# KEY_1_0.net
KiCad netlist of a schematic drawn in EAGLE
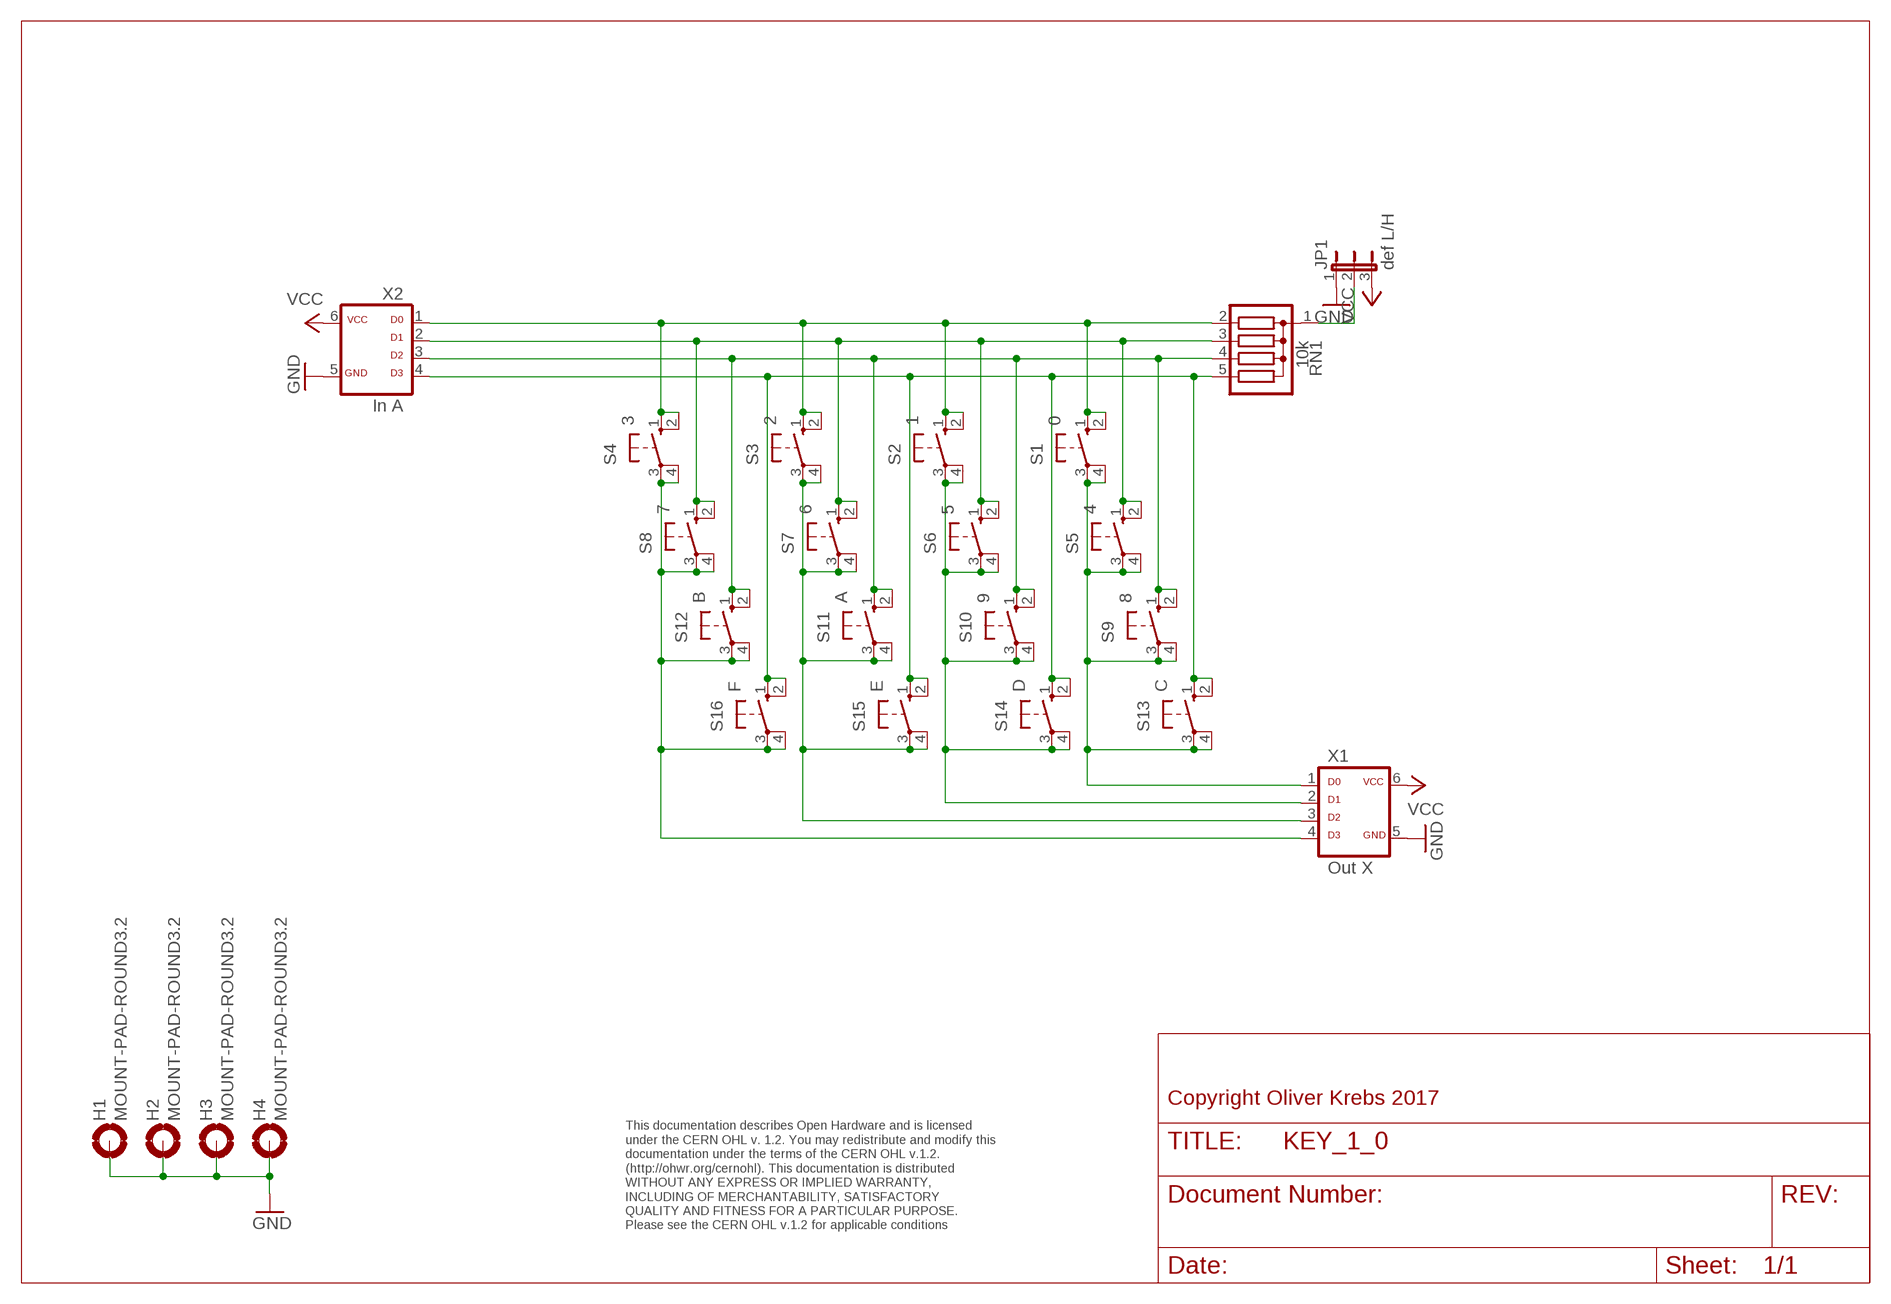
[diagram p0: schematic, sheet 1]

(export (version "E")
  (design (tool "Eeschema 10.0.6"))
  (components
    (comp (ref "H1")
      (value "MOUNT-PAD-ROUND3.2")
      (footprint "eagle-import:3,2-PAD")
      (libsource (lib "eagle-import") (part "MOUNT-PAD-ROUND3.2"))
    )
    (comp (ref "H2")
      (value "MOUNT-PAD-ROUND3.2")
      (footprint "eagle-import:3,2-PAD")
      (libsource (lib "eagle-import") (part "MOUNT-PAD-ROUND3.2"))
    )
    (comp (ref "H3")
      (value "MOUNT-PAD-ROUND3.2")
      (footprint "eagle-import:3,2-PAD")
      (libsource (lib "eagle-import") (part "MOUNT-PAD-ROUND3.2"))
    )
    (comp (ref "H4")
      (value "MOUNT-PAD-ROUND3.2")
      (footprint "eagle-import:3,2-PAD")
      (libsource (lib "eagle-import") (part "MOUNT-PAD-ROUND3.2"))
    )
    (comp (ref "JP1")
      (value "def L/H")
      (footprint "eagle-import:JP2-U")
      (libsource (lib "eagle-import") (part "JP2EJP2-U"))
    )
    (comp (ref "RN1")
      (value "10k")
      (footprint "eagle-import:SIL5")
      (libsource (lib "eagle-import") (part "G04R"))
    )
    (comp (ref "S1")
      (value "0")
      (footprint "eagle-import:B3F-10XX")
      (fields (field (name "MPN") "B3F-1000"))
      (libsource (lib "eagle-import") (part "10-XX"))
    )
    (comp (ref "S2")
      (value "1")
      (footprint "eagle-import:B3F-10XX")
      (fields (field (name "MPN") "B3F-1000"))
      (libsource (lib "eagle-import") (part "10-XX"))
    )
    (comp (ref "S3")
      (value "2")
      (footprint "eagle-import:B3F-10XX")
      (fields (field (name "MPN") "B3F-1000"))
      (libsource (lib "eagle-import") (part "10-XX"))
    )
    (comp (ref "S4")
      (value "3")
      (footprint "eagle-import:B3F-10XX")
      (fields (field (name "MPN") "B3F-1000"))
      (libsource (lib "eagle-import") (part "10-XX"))
    )
    (comp (ref "S5")
      (value "4")
      (footprint "eagle-import:B3F-10XX")
      (fields (field (name "MPN") "B3F-1000"))
      (libsource (lib "eagle-import") (part "10-XX"))
    )
    (comp (ref "S6")
      (value "5")
      (footprint "eagle-import:B3F-10XX")
      (fields (field (name "MPN") "B3F-1000"))
      (libsource (lib "eagle-import") (part "10-XX"))
    )
    (comp (ref "S7")
      (value "6")
      (footprint "eagle-import:B3F-10XX")
      (fields (field (name "MPN") "B3F-1000"))
      (libsource (lib "eagle-import") (part "10-XX"))
    )
    (comp (ref "S8")
      (value "7")
      (footprint "eagle-import:B3F-10XX")
      (fields (field (name "MPN") "B3F-1000"))
      (libsource (lib "eagle-import") (part "10-XX"))
    )
    (comp (ref "S9")
      (value "8")
      (footprint "eagle-import:B3F-10XX")
      (fields (field (name "MPN") "B3F-1000"))
      (libsource (lib "eagle-import") (part "10-XX"))
    )
    (comp (ref "S10")
      (value "9")
      (footprint "eagle-import:B3F-10XX")
      (fields (field (name "MPN") "B3F-1000"))
      (libsource (lib "eagle-import") (part "10-XX"))
    )
    (comp (ref "S11")
      (value "A")
      (footprint "eagle-import:B3F-10XX")
      (fields (field (name "MPN") "B3F-1000"))
      (libsource (lib "eagle-import") (part "10-XX"))
    )
    (comp (ref "S12")
      (value "B")
      (footprint "eagle-import:B3F-10XX")
      (fields (field (name "MPN") "B3F-1000"))
      (libsource (lib "eagle-import") (part "10-XX"))
    )
    (comp (ref "S13")
      (value "C")
      (footprint "eagle-import:B3F-10XX")
      (fields (field (name "MPN") "B3F-1000"))
      (libsource (lib "eagle-import") (part "10-XX"))
    )
    (comp (ref "S14")
      (value "D")
      (footprint "eagle-import:B3F-10XX")
      (fields (field (name "MPN") "B3F-1000"))
      (libsource (lib "eagle-import") (part "10-XX"))
    )
    (comp (ref "S15")
      (value "E")
      (footprint "eagle-import:B3F-10XX")
      (fields (field (name "MPN") "B3F-1000"))
      (libsource (lib "eagle-import") (part "10-XX"))
    )
    (comp (ref "S16")
      (value "F")
      (footprint "eagle-import:B3F-10XX")
      (fields (field (name "MPN") "B3F-1000"))
      (libsource (lib "eagle-import") (part "10-XX"))
    )
    (comp (ref "X1")
      (value "Out X")
      (footprint "eagle-import:ML-6")
      (libsource (lib "eagle-import") (part "ML6D"))
    )
    (comp (ref "X2")
      (value "In A")
      (footprint "eagle-import:ML-6")
      (libsource (lib "eagle-import") (part "ML6D"))
    )
  )
  (nets
    (net (code "1") (name "GND") (class "Default")
      (node (ref "H1") (pin "B3,2") (pinfunction "MOUNT_B3,2") (pintype "passive"))
      (node (ref "H2") (pin "B3,2") (pinfunction "MOUNT_B3,2") (pintype "passive"))
      (node (ref "H3") (pin "B3,2") (pinfunction "MOUNT_B3,2") (pintype "passive"))
      (node (ref "H4") (pin "B3,2") (pinfunction "MOUNT_B3,2") (pintype "passive"))
      (node (ref "JP1") (pin "1") (pinfunction "1_1") (pintype "passive"))
      (node (ref "X1") (pin "5") (pinfunction "5_5") (pintype "passive"))
      (node (ref "X2") (pin "5") (pinfunction "5_5") (pintype "passive"))
    )
    (net (code "2") (name "Net-(JP1-Pad2)") (class "Default")
      (node (ref "JP1") (pin "2") (pinfunction "2_2") (pintype "passive"))
      (node (ref "RN1") (pin "1") (pinfunction "1_1") (pintype "passive"))
    )
    (net (code "3") (name "Net-(S1-P)") (class "Default")
      (node (ref "S1") (pin "3") (pinfunction "P_3") (pintype "passive"))
      (node (ref "S1") (pin "4") (pinfunction "P1_4") (pintype "passive"))
      (node (ref "S13") (pin "3") (pinfunction "P_3") (pintype "passive"))
      (node (ref "S13") (pin "4") (pinfunction "P1_4") (pintype "passive"))
      (node (ref "S5") (pin "3") (pinfunction "P_3") (pintype "passive"))
      (node (ref "S5") (pin "4") (pinfunction "P1_4") (pintype "passive"))
      (node (ref "S9") (pin "3") (pinfunction "P_3") (pintype "passive"))
      (node (ref "S9") (pin "4") (pinfunction "P1_4") (pintype "passive"))
      (node (ref "X1") (pin "1") (pinfunction "1_1") (pintype "passive"))
    )
    (net (code "4") (name "Net-(S1-S)") (class "Default")
      (node (ref "RN1") (pin "2") (pinfunction "2_2") (pintype "passive"))
      (node (ref "S1") (pin "1") (pinfunction "S_1") (pintype "passive"))
      (node (ref "S1") (pin "2") (pinfunction "S1_2") (pintype "passive"))
      (node (ref "S2") (pin "1") (pinfunction "S_1") (pintype "passive"))
      (node (ref "S2") (pin "2") (pinfunction "S1_2") (pintype "passive"))
      (node (ref "S3") (pin "1") (pinfunction "S_1") (pintype "passive"))
      (node (ref "S3") (pin "2") (pinfunction "S1_2") (pintype "passive"))
      (node (ref "S4") (pin "1") (pinfunction "S_1") (pintype "passive"))
      (node (ref "S4") (pin "2") (pinfunction "S1_2") (pintype "passive"))
      (node (ref "X2") (pin "1") (pinfunction "1_1") (pintype "passive"))
    )
    (net (code "5") (name "Net-(S5-S)") (class "Default")
      (node (ref "RN1") (pin "3") (pinfunction "3_3") (pintype "passive"))
      (node (ref "S5") (pin "1") (pinfunction "S_1") (pintype "passive"))
      (node (ref "S5") (pin "2") (pinfunction "S1_2") (pintype "passive"))
      (node (ref "S6") (pin "1") (pinfunction "S_1") (pintype "passive"))
      (node (ref "S6") (pin "2") (pinfunction "S1_2") (pintype "passive"))
      (node (ref "S7") (pin "1") (pinfunction "S_1") (pintype "passive"))
      (node (ref "S7") (pin "2") (pinfunction "S1_2") (pintype "passive"))
      (node (ref "S8") (pin "1") (pinfunction "S_1") (pintype "passive"))
      (node (ref "S8") (pin "2") (pinfunction "S1_2") (pintype "passive"))
      (node (ref "X2") (pin "2") (pinfunction "2_2") (pintype "passive"))
    )
    (net (code "6") (name "Net-(S10-P)") (class "Default")
      (node (ref "S10") (pin "3") (pinfunction "P_3") (pintype "passive"))
      (node (ref "S10") (pin "4") (pinfunction "P1_4") (pintype "passive"))
      (node (ref "S14") (pin "3") (pinfunction "P_3") (pintype "passive"))
      (node (ref "S14") (pin "4") (pinfunction "P1_4") (pintype "passive"))
      (node (ref "S2") (pin "3") (pinfunction "P_3") (pintype "passive"))
      (node (ref "S2") (pin "4") (pinfunction "P1_4") (pintype "passive"))
      (node (ref "S6") (pin "3") (pinfunction "P_3") (pintype "passive"))
      (node (ref "S6") (pin "4") (pinfunction "P1_4") (pintype "passive"))
      (node (ref "X1") (pin "2") (pinfunction "2_2") (pintype "passive"))
    )
    (net (code "7") (name "Net-(S10-S)") (class "Default")
      (node (ref "RN1") (pin "4") (pinfunction "4_4") (pintype "passive"))
      (node (ref "S10") (pin "1") (pinfunction "S_1") (pintype "passive"))
      (node (ref "S10") (pin "2") (pinfunction "S1_2") (pintype "passive"))
      (node (ref "S11") (pin "1") (pinfunction "S_1") (pintype "passive"))
      (node (ref "S11") (pin "2") (pinfunction "S1_2") (pintype "passive"))
      (node (ref "S12") (pin "1") (pinfunction "S_1") (pintype "passive"))
      (node (ref "S12") (pin "2") (pinfunction "S1_2") (pintype "passive"))
      (node (ref "S9") (pin "1") (pinfunction "S_1") (pintype "passive"))
      (node (ref "S9") (pin "2") (pinfunction "S1_2") (pintype "passive"))
      (node (ref "X2") (pin "3") (pinfunction "3_3") (pintype "passive"))
    )
    (net (code "8") (name "Net-(S11-P)") (class "Default")
      (node (ref "S11") (pin "3") (pinfunction "P_3") (pintype "passive"))
      (node (ref "S11") (pin "4") (pinfunction "P1_4") (pintype "passive"))
      (node (ref "S15") (pin "3") (pinfunction "P_3") (pintype "passive"))
      (node (ref "S15") (pin "4") (pinfunction "P1_4") (pintype "passive"))
      (node (ref "S3") (pin "3") (pinfunction "P_3") (pintype "passive"))
      (node (ref "S3") (pin "4") (pinfunction "P1_4") (pintype "passive"))
      (node (ref "S7") (pin "3") (pinfunction "P_3") (pintype "passive"))
      (node (ref "S7") (pin "4") (pinfunction "P1_4") (pintype "passive"))
      (node (ref "X1") (pin "3") (pinfunction "3_3") (pintype "passive"))
    )
    (net (code "9") (name "Net-(S12-P)") (class "Default")
      (node (ref "S12") (pin "3") (pinfunction "P_3") (pintype "passive"))
      (node (ref "S12") (pin "4") (pinfunction "P1_4") (pintype "passive"))
      (node (ref "S16") (pin "3") (pinfunction "P_3") (pintype "passive"))
      (node (ref "S16") (pin "4") (pinfunction "P1_4") (pintype "passive"))
      (node (ref "S4") (pin "3") (pinfunction "P_3") (pintype "passive"))
      (node (ref "S4") (pin "4") (pinfunction "P1_4") (pintype "passive"))
      (node (ref "S8") (pin "3") (pinfunction "P_3") (pintype "passive"))
      (node (ref "S8") (pin "4") (pinfunction "P1_4") (pintype "passive"))
      (node (ref "X1") (pin "4") (pinfunction "4_4") (pintype "passive"))
    )
    (net (code "10") (name "Net-(S13-S)") (class "Default")
      (node (ref "RN1") (pin "5") (pinfunction "5_5") (pintype "passive"))
      (node (ref "S13") (pin "1") (pinfunction "S_1") (pintype "passive"))
      (node (ref "S13") (pin "2") (pinfunction "S1_2") (pintype "passive"))
      (node (ref "S14") (pin "1") (pinfunction "S_1") (pintype "passive"))
      (node (ref "S14") (pin "2") (pinfunction "S1_2") (pintype "passive"))
      (node (ref "S15") (pin "1") (pinfunction "S_1") (pintype "passive"))
      (node (ref "S15") (pin "2") (pinfunction "S1_2") (pintype "passive"))
      (node (ref "S16") (pin "1") (pinfunction "S_1") (pintype "passive"))
      (node (ref "S16") (pin "2") (pinfunction "S1_2") (pintype "passive"))
      (node (ref "X2") (pin "4") (pinfunction "4_4") (pintype "passive"))
    )
    (net (code "11") (name "VCC") (class "Default")
      (node (ref "JP1") (pin "3") (pinfunction "3_3") (pintype "passive"))
      (node (ref "X1") (pin "6") (pinfunction "6_6") (pintype "passive"))
      (node (ref "X2") (pin "6") (pinfunction "6_6") (pintype "passive"))
    )
  )
)
